# signal-2btn.net
KiCad netlist of a schematic drawn in EAGLE
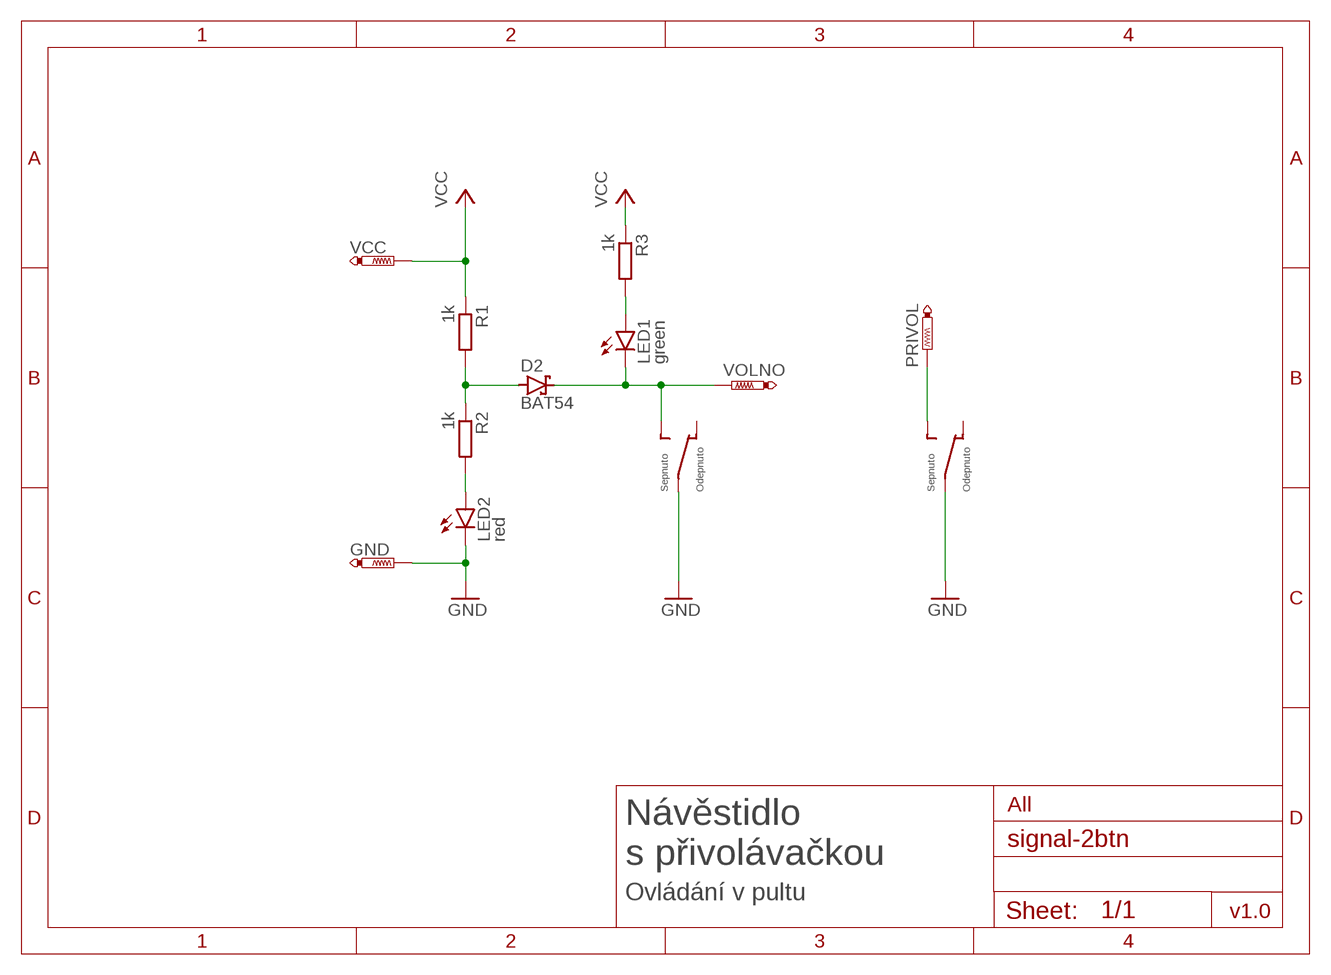
[diagram p0: schematic, sheet 1]

(export (version "E")
  (design (tool "Eeschema 10.0.6"))
  (components
    (comp (ref "D2")
      (value "BAT54")
      (footprint "eagle-import:SOT23")
      (libsource (lib "eagle-import") (part "BAT54"))
    )
    (comp (ref "GND")
      (value "PTR1PAD1-13Y")
      (footprint "eagle-import:P1-13Y")
      (libsource (lib "eagle-import") (part "PTR1PAD1-13Y"))
    )
    (comp (ref "LED1")
      (value "green")
      (footprint "eagle-import:LED3MM")
      (libsource (lib "eagle-import") (part "LED3MM"))
    )
    (comp (ref "LED2")
      (value "red")
      (footprint "eagle-import:LED3MM")
      (libsource (lib "eagle-import") (part "LED3MM"))
    )
    (comp (ref "R1")
      (value "1k")
      (footprint "eagle-import:R0805")
      (libsource (lib "eagle-import") (part "R-EU_R0805"))
    )
    (comp (ref "R2")
      (value "1k")
      (footprint "eagle-import:R0805")
      (libsource (lib "eagle-import") (part "R-EU_R0805"))
    )
    (comp (ref "R3")
      (value "1k")
      (footprint "eagle-import:R0805")
      (libsource (lib "eagle-import") (part "R-EU_R0805"))
    )
    (comp (ref "S1")
      (value "HORASPINAC")
      (footprint "eagle-import:HORASPINAC")
      (libsource (lib "eagle-import") (part "HORASPINAC"))
    )
    (comp (ref "S2")
      (value "HORASPINAC")
      (footprint "eagle-import:HORASPINAC")
      (libsource (lib "eagle-import") (part "HORASPINAC"))
    )
    (comp (ref "SIGNAL")
      (value "PTR1PAD1-13Y")
      (footprint "eagle-import:P1-13Y")
      (libsource (lib "eagle-import") (part "PTR1PAD1-13Y"))
    )
    (comp (ref "SIGNAL1")
      (value "PTR1PAD1-13Y")
      (footprint "eagle-import:P1-13Y")
      (libsource (lib "eagle-import") (part "PTR1PAD1-13Y"))
    )
    (comp (ref "VCC")
      (value "PTR1PAD1-13Y")
      (footprint "eagle-import:P1-13Y")
      (libsource (lib "eagle-import") (part "PTR1PAD1-13Y"))
    )
  )
  (nets
    (net (code "1") (name "/PRIVOL") (class "Default")
      (node (ref "S2") (pin "SEPNUTO1") (pinfunction "SEPNUTO_SEPNUTO1") (pintype "passive"))
      (node (ref "SIGNAL1") (pin "TP") (pinfunction "TP_TP") (pintype "input"))
    )
    (net (code "2") (name "/VOLNO") (class "Default")
      (node (ref "D2") (pin "3") (pinfunction "C_3") (pintype "passive"))
      (node (ref "LED1") (pin "K") (pinfunction "C_K") (pintype "passive"))
      (node (ref "S1") (pin "SEPNUTO1") (pinfunction "SEPNUTO_SEPNUTO1") (pintype "passive"))
      (node (ref "SIGNAL") (pin "TP") (pinfunction "TP_TP") (pintype "input"))
    )
    (net (code "3") (name "GND") (class "Default")
      (node (ref "GND") (pin "TP") (pinfunction "TP_TP") (pintype "input"))
      (node (ref "LED2") (pin "K") (pinfunction "C_K") (pintype "passive"))
      (node (ref "S1") (pin "NAPAJENI1") (pinfunction "NAPAJENI_NAPAJENI1") (pintype "passive"))
      (node (ref "S2") (pin "NAPAJENI1") (pinfunction "NAPAJENI_NAPAJENI1") (pintype "passive"))
    )
    (net (code "4") (name "Net-(D2-A)") (class "Default")
      (node (ref "D2") (pin "1") (pinfunction "A_1") (pintype "passive"))
      (node (ref "R1") (pin "2") (pinfunction "2_2") (pintype "passive"))
      (node (ref "R2") (pin "1") (pinfunction "1_1") (pintype "passive"))
    )
    (net (code "5") (name "Net-(LED1-PadA)") (class "Default")
      (node (ref "LED1") (pin "A") (pinfunction "A_A") (pintype "passive"))
      (node (ref "R3") (pin "2") (pinfunction "2_2") (pintype "passive"))
    )
    (net (code "6") (name "Net-(LED2-PadA)") (class "Default")
      (node (ref "LED2") (pin "A") (pinfunction "A_A") (pintype "passive"))
      (node (ref "R2") (pin "2") (pinfunction "2_2") (pintype "passive"))
    )
    (net (code "7") (name "VCC") (class "Default")
      (node (ref "R1") (pin "1") (pinfunction "1_1") (pintype "passive"))
      (node (ref "R3") (pin "1") (pinfunction "1_1") (pintype "passive"))
      (node (ref "VCC") (pin "TP") (pinfunction "TP_TP") (pintype "input"))
    )
    (net (code "8") (name "unconnected-(S1A-ODEPNUTO-PadODEPNUTO1)") (class "Default")
      (node (ref "S1") (pin "ODEPNUTO1") (pinfunction "ODEPNUTO_ODEPNUTO1") (pintype "passive"))
    )
    (net (code "9") (name "unconnected-(S2A-ODEPNUTO-PadODEPNUTO1)") (class "Default")
      (node (ref "S2") (pin "ODEPNUTO1") (pinfunction "ODEPNUTO_ODEPNUTO1") (pintype "passive"))
    )
  )
)
